# Nh_ng.net
KiCad netlist of a schematic drawn in Altium Designer
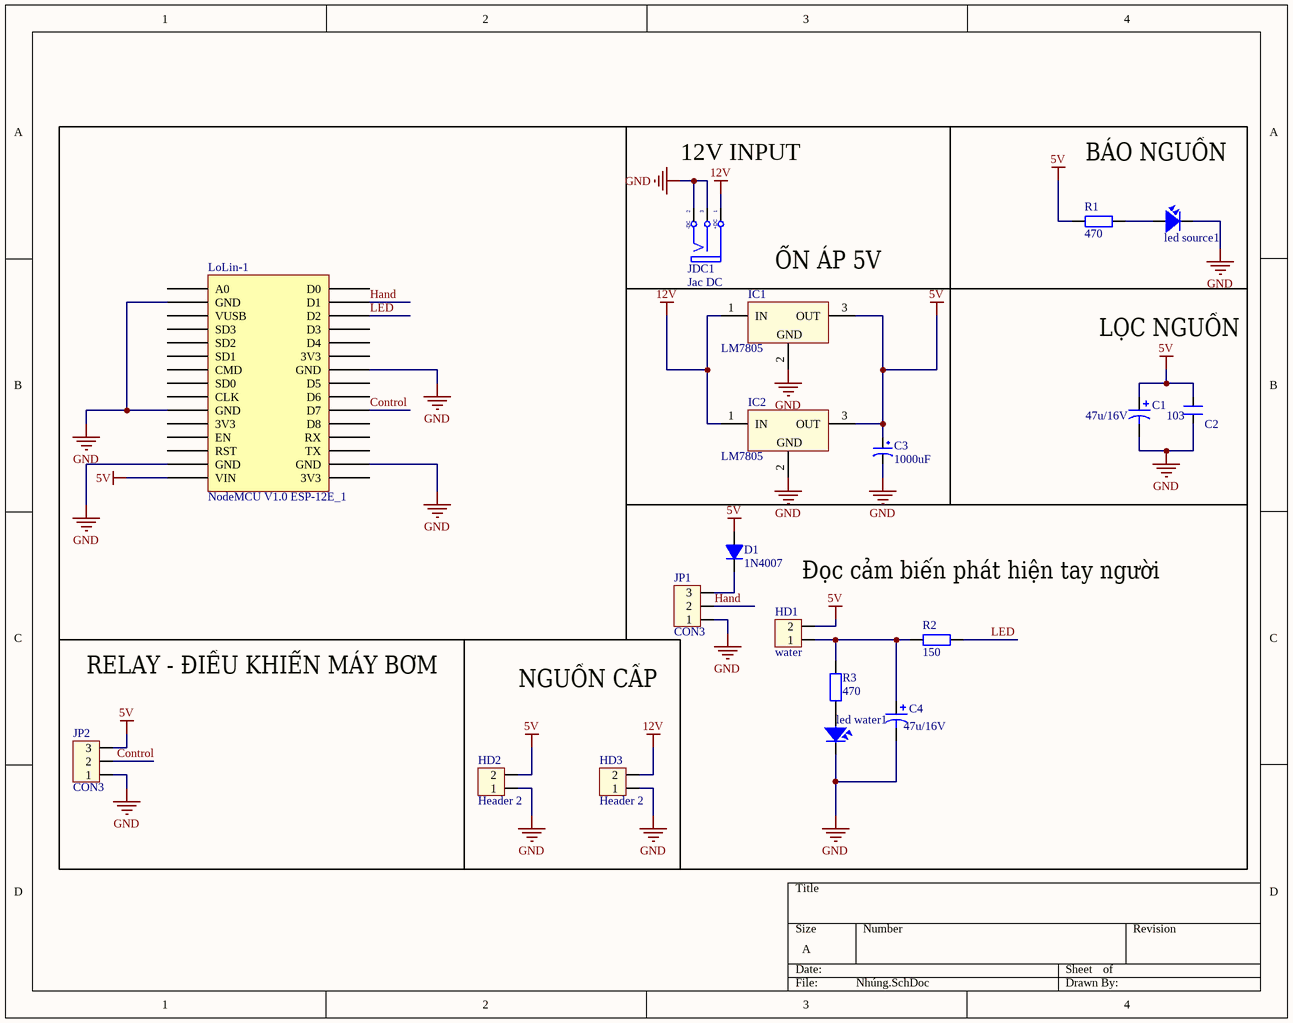
[diagram p0: Nhúng.SchDoc]

(export (version "E")
  (design (tool "Eeschema 10.0.6"))
  (components
    (comp (ref "C1")
      (value "47u/16V")
      (footprint "C3MM")
      (description "Polarized Capacitor (Axial)")
      (fields (field (name "PUBLISHER") "Altium Limited"))
      (libsource (lib "My library altium") (part "Cap Pol"))
    )
    (comp (ref "C2") (value "103") (footprint "CN1") (libsource (lib "My library altium") (part "CAP gom")))
    (comp (ref "C3")
      (value "1000uF")
      (footprint "CP1/2")
      (description "Cap P  0,1uF < 22uF , 16 - 50V")
      (libsource (lib "syhaunguyen") (part "CP1"))
    )
    (comp (ref "C4")
      (value "47u/16V")
      (footprint "C3MM")
      (description "Polarized Capacitor (Axial)")
      (fields (field (name "PUBLISHER") "Altium Limited"))
      (libsource (lib "My library altium") (part "Cap Pol"))
    )
    (comp (ref "D1")
      (value "1N4007")
      (footprint "D1A")
      (description "Diode 1A")
      (libsource (lib "syhaunguyen") (part "D1A"))
    )
    (comp (ref "HD1")
      (value "water")
      (footprint "HED2")
      (description "Header 2 (Green)")
      (libsource (lib "My library altium") (part "Header 2"))
    )
    (comp (ref "HD2")
      (value "Header 2")
      (footprint "HED2")
      (description "Header 2 (Green)")
      (libsource (lib "My library altium") (part "Header 2"))
    )
    (comp (ref "HD3")
      (value "Header 2")
      (footprint "HED2")
      (description "Header 2 (Green)")
      (libsource (lib "My library altium") (part "Header 2"))
    )
    (comp (ref "IC1")
      (value "LM7805")
      (footprint "QTO-220")
      (description "On ap +, from + 5 to + 24VDC")
      (libsource (lib "My library altium") (part "LM78xx"))
    )
    (comp (ref "IC2")
      (value "LM7805")
      (footprint "QTO-220")
      (description "On ap +, from + 5 to + 24VDC")
      (libsource (lib "My library altium") (part "LM78xx"))
    )
    (comp (ref "JDC1")
      (value "Jac DC")
      (footprint "DC-IN")
      (description "Jac DC input")
      (libsource (lib "syhaunguyen") (part "DCIN"))
    )
    (comp (ref "JP1")
      (value "CON3")
      (footprint "jam3")
      (description "jam 3")
      (libsource (lib "My library altium") (part "jam 3"))
    )
    (comp (ref "JP2")
      (value "CON3")
      (footprint "jam3")
      (description "jam 3")
      (libsource (lib "My library altium") (part "jam 3"))
    )
    (comp (ref "led source1")
      (value "LED")
      (footprint "LED-3")
      (description "LED Single colour Green and Red")
      (libsource (lib "syhaunguyen") (part "LED"))
    )
    (comp (ref "led water1")
      (value "LED")
      (footprint "LED-3")
      (description "LED Single colour Green and Red")
      (libsource (lib "syhaunguyen") (part "LED"))
    )
    (comp (ref "LoLin-1")
      (value "NodeMCU V1.0 ESP-12E_1")
      (footprint "LoLin NodeMcu V3")
      (description "LoLin NodeMCU V3")
      (libsource (lib "nodemcu") (part "NodeMCU V1.0 ESP-12E_1"))
    )
    (comp (ref "R1")
      (value "470")
      (footprint "R1/4W")
      (description "Resistor 1/4W")
      (libsource (lib "syhaunguyen") (part "R1/4W"))
    )
    (comp (ref "R2")
      (value "150")
      (footprint "R1/4W")
      (description "Resistor 1/4W")
      (libsource (lib "syhaunguyen") (part "R1/4W"))
    )
    (comp (ref "R3")
      (value "470")
      (footprint "R1/4W")
      (description "Resistor 1/4W")
      (libsource (lib "syhaunguyen") (part "R1/4W"))
    )
  )
  (nets
    (net (code "1") (name "/Control") (class "Default")
      (node (ref "JP2") (pin "2") (pinfunction "2_2") (pintype "passive"))
      (node (ref "LoLin-1") (pin "D7") (pinfunction "D7_D7") (pintype "passive"))
    )
    (net (code "2") (name "/Hand") (class "Default")
      (node (ref "JP1") (pin "2") (pinfunction "2_2") (pintype "passive"))
      (node (ref "LoLin-1") (pin "D1") (pinfunction "D1_D1") (pintype "passive"))
    )
    (net (code "3") (name "/LED") (class "Default")
      (node (ref "LoLin-1") (pin "D2") (pinfunction "D2_D2") (pintype "passive"))
      (node (ref "R2") (pin "1") (pinfunction "1_1") (pintype "passive"))
    )
    (net (code "4") (name "5V") (class "Default")
      (node (ref "C1") (pin "1") (pinfunction "1_1") (pintype "passive"))
      (node (ref "C2") (pin "2") (pinfunction "2_2") (pintype "passive"))
      (node (ref "C3") (pin "1") (pinfunction "1_1") (pintype "passive"))
      (node (ref "D1") (pin "1") (pinfunction "A_1") (pintype "passive"))
      (node (ref "HD1") (pin "2") (pinfunction "2_2") (pintype "passive"))
      (node (ref "HD2") (pin "2") (pinfunction "2_2") (pintype "passive"))
      (node (ref "IC1") (pin "3") (pinfunction "OUT_3") (pintype "passive"))
      (node (ref "IC2") (pin "3") (pinfunction "OUT_3") (pintype "passive"))
      (node (ref "JP2") (pin "3") (pinfunction "3_3") (pintype "passive"))
      (node (ref "LoLin-1") (pin "VIN") (pinfunction "VIN_VIN") (pintype "passive"))
      (node (ref "R1") (pin "1") (pinfunction "1_1") (pintype "passive"))
    )
    (net (code "5") (name "12V") (class "Default")
      (node (ref "HD3") (pin "2") (pinfunction "2_2") (pintype "passive"))
      (node (ref "IC1") (pin "1") (pinfunction "IN_1") (pintype "passive"))
      (node (ref "IC2") (pin "1") (pinfunction "IN_1") (pintype "passive"))
      (node (ref "JDC1") (pin "1") (pinfunction "T_1") (pintype "passive"))
    )
    (net (code "6") (name "GND") (class "Default")
      (node (ref "C1") (pin "2") (pinfunction "2_2") (pintype "passive"))
      (node (ref "C2") (pin "1") (pinfunction "1_1") (pintype "passive"))
      (node (ref "C3") (pin "2") (pinfunction "2_2") (pintype "passive"))
      (node (ref "C4") (pin "2") (pinfunction "2_2") (pintype "passive"))
      (node (ref "HD2") (pin "1") (pinfunction "1_1") (pintype "passive"))
      (node (ref "HD3") (pin "1") (pinfunction "1_1") (pintype "passive"))
      (node (ref "IC1") (pin "2") (pinfunction "GND_2") (pintype "passive"))
      (node (ref "IC2") (pin "2") (pinfunction "GND_2") (pintype "passive"))
      (node (ref "JDC1") (pin "2") (pinfunction "TN_2") (pintype "passive"))
      (node (ref "JDC1") (pin "3") (pinfunction "S_3") (pintype "power_in"))
      (node (ref "JP1") (pin "1") (pinfunction "1_1") (pintype "passive"))
      (node (ref "JP2") (pin "1") (pinfunction "1_1") (pintype "passive"))
      (node (ref "LoLin-1") (pin "GND") (pinfunction "GND_GND") (pintype "passive"))
      (node (ref "led source1") (pin "2") (pinfunction "2_2") (pintype "passive"))
      (node (ref "led water1") (pin "2") (pinfunction "2_2") (pintype "passive"))
    )
    (net (code "7") (name "Net-(C4-Pad1)") (class "Default")
      (node (ref "C4") (pin "1") (pinfunction "1_1") (pintype "passive"))
      (node (ref "HD1") (pin "1") (pinfunction "1_1") (pintype "passive"))
      (node (ref "R2") (pin "2") (pinfunction "2_2") (pintype "passive"))
      (node (ref "R3") (pin "2") (pinfunction "2_2") (pintype "passive"))
    )
    (net (code "8") (name "Net-(D1-K)") (class "Default")
      (node (ref "D1") (pin "2") (pinfunction "K_2") (pintype "passive"))
      (node (ref "JP1") (pin "3") (pinfunction "3_3") (pintype "passive"))
    )
    (net (code "9") (name "Net-(R1-Pad2)") (class "Default")
      (node (ref "R1") (pin "2") (pinfunction "2_2") (pintype "passive"))
      (node (ref "led source1") (pin "1") (pinfunction "1_1") (pintype "passive"))
    )
    (net (code "10") (name "Net-(R3-Pad1)") (class "Default")
      (node (ref "R3") (pin "1") (pinfunction "1_1") (pintype "passive"))
      (node (ref "led water1") (pin "1") (pinfunction "1_1") (pintype "passive"))
    )
    (net (code "11") (name "unconnected-(LoLin-1-Pad3V3)") (class "Default")
      (node (ref "LoLin-1") (pin "3V3") (pinfunction "3V3_3V3") (pintype "passive"))
    )
    (net (code "12") (name "unconnected-(LoLin-1-Pad3V3)_1") (class "Default")
      (node (ref "LoLin-1") (pin "3V3") (pinfunction "3V3_3V3") (pintype "passive"))
    )
    (net (code "13") (name "unconnected-(LoLin-1-Pad3V3)_2") (class "Default")
      (node (ref "LoLin-1") (pin "3V3") (pinfunction "3V3_3V3") (pintype "passive"))
    )
    (net (code "14") (name "unconnected-(LoLin-1-PadA0)") (class "Default")
      (node (ref "LoLin-1") (pin "A0") (pinfunction "A0_A0") (pintype "passive"))
    )
    (net (code "15") (name "unconnected-(LoLin-1-PadCLK)") (class "Default")
      (node (ref "LoLin-1") (pin "CLK") (pinfunction "CLK_CLK") (pintype "passive"))
    )
    (net (code "16") (name "unconnected-(LoLin-1-PadCMD)") (class "Default")
      (node (ref "LoLin-1") (pin "CMD") (pinfunction "CMD_CMD") (pintype "passive"))
    )
    (net (code "17") (name "unconnected-(LoLin-1-PadD0)") (class "Default")
      (node (ref "LoLin-1") (pin "D0") (pinfunction "D0_D0") (pintype "passive"))
    )
    (net (code "18") (name "unconnected-(LoLin-1-PadD3)") (class "Default")
      (node (ref "LoLin-1") (pin "D3") (pinfunction "D3_D3") (pintype "passive"))
    )
    (net (code "19") (name "unconnected-(LoLin-1-PadD4)") (class "Default")
      (node (ref "LoLin-1") (pin "D4") (pinfunction "D4_D4") (pintype "passive"))
    )
    (net (code "20") (name "unconnected-(LoLin-1-PadD5)") (class "Default")
      (node (ref "LoLin-1") (pin "D5") (pinfunction "D5_D5") (pintype "passive"))
    )
    (net (code "21") (name "unconnected-(LoLin-1-PadD6)") (class "Default")
      (node (ref "LoLin-1") (pin "D6") (pinfunction "D6_D6") (pintype "passive"))
    )
    (net (code "22") (name "unconnected-(LoLin-1-PadD8)") (class "Default")
      (node (ref "LoLin-1") (pin "D8") (pinfunction "D8_D8") (pintype "passive"))
    )
    (net (code "23") (name "unconnected-(LoLin-1-PadEN)") (class "Default")
      (node (ref "LoLin-1") (pin "EN") (pinfunction "EN_EN") (pintype "passive"))
    )
    (net (code "24") (name "unconnected-(LoLin-1-PadRST)") (class "Default")
      (node (ref "LoLin-1") (pin "RST") (pinfunction "RST_RST") (pintype "passive"))
    )
    (net (code "25") (name "unconnected-(LoLin-1-PadRX)") (class "Default")
      (node (ref "LoLin-1") (pin "RX") (pinfunction "RX_RX") (pintype "passive"))
    )
    (net (code "26") (name "unconnected-(LoLin-1-PadSD0)") (class "Default")
      (node (ref "LoLin-1") (pin "SD0") (pinfunction "SD0_SD0") (pintype "passive"))
    )
    (net (code "27") (name "unconnected-(LoLin-1-PadSD1)") (class "Default")
      (node (ref "LoLin-1") (pin "SD1") (pinfunction "SD1_SD1") (pintype "passive"))
    )
    (net (code "28") (name "unconnected-(LoLin-1-PadSD2)") (class "Default")
      (node (ref "LoLin-1") (pin "SD2") (pinfunction "SD2_SD2") (pintype "passive"))
    )
    (net (code "29") (name "unconnected-(LoLin-1-PadSD3)") (class "Default")
      (node (ref "LoLin-1") (pin "SD3") (pinfunction "SD3_SD3") (pintype "passive"))
    )
    (net (code "30") (name "unconnected-(LoLin-1-PadTX)") (class "Default")
      (node (ref "LoLin-1") (pin "TX") (pinfunction "TX_TX") (pintype "passive"))
    )
    (net (code "31") (name "unconnected-(LoLin-1-PadVUSB)") (class "Default")
      (node (ref "LoLin-1") (pin "VUSB") (pinfunction "VUSB_VUSB") (pintype "passive"))
    )
  )
)
